# stm32_tiny_swd.net
KiCad netlist of a schematic drawn in EAGLE
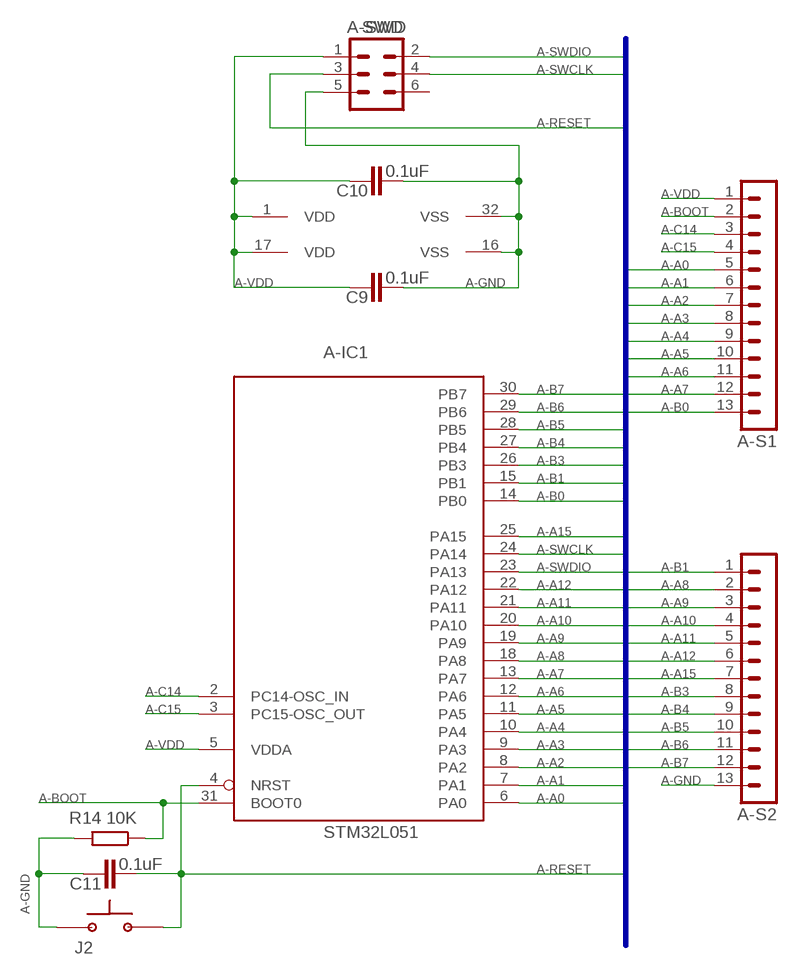
[diagram p0: schematic, sheet 1]

(export (version "E")
  (design (tool "Eeschema 10.0.6"))
  (components
    (comp (ref "A-IC1")
      (value "STM32L051")
      (footprint "eagle-import:LQFP32")
      (libsource (lib "eagle-import") (part "STM32L051KT8"))
    )
    (comp (ref "A-S1")
      (value "MA13-1")
      (footprint "eagle-import:MA13-1")
      (libsource (lib "eagle-import") (part "MA13-1"))
    )
    (comp (ref "A-S2")
      (value "MA13-1")
      (footprint "eagle-import:MA13-1")
      (libsource (lib "eagle-import") (part "MA13-1"))
    )
    (comp (ref "A-SWD")
      (value "SWD")
      (footprint "eagle-import:MA03-2")
      (libsource (lib "eagle-import") (part "MA03-2"))
    )
    (comp (ref "C9")
      (value "0.1uF")
      (footprint "eagle-import:C0805")
      (libsource (lib "eagle-import") (part "C-EUC0805"))
    )
    (comp (ref "C10")
      (value "0.1uF")
      (footprint "eagle-import:C0805")
      (libsource (lib "eagle-import") (part "C-EUC0805"))
    )
    (comp (ref "C11")
      (value "0.1uF")
      (footprint "eagle-import:C0805")
      (libsource (lib "eagle-import") (part "C-EUC0805"))
    )
    (comp (ref "J2")
      (value "BUTTON-FSM14JRT")
      (footprint "eagle-import:BUTTON-FSM14JRT")
      (libsource (lib "eagle-import") (part "BUTTON-FSM14JRT"))
    )
    (comp (ref "R14")
      (value "10K")
      (footprint "eagle-import:R0805")
      (libsource (lib "eagle-import") (part "R-EU_R0805"))
    )
  )
  (nets
    (net (code "1") (name "/A-A0") (class "Default")
      (node (ref "A-IC1") (pin "6") (pinfunction "PA0_6") (pintype "bidirectional"))
      (node (ref "A-S1") (pin "5") (pinfunction "5_5") (pintype "passive"))
    )
    (net (code "2") (name "/A-A1") (class "Default")
      (node (ref "A-IC1") (pin "7") (pinfunction "PA1_7") (pintype "bidirectional"))
      (node (ref "A-S1") (pin "6") (pinfunction "6_6") (pintype "passive"))
    )
    (net (code "3") (name "/A-A2") (class "Default")
      (node (ref "A-IC1") (pin "8") (pinfunction "PA2_8") (pintype "bidirectional"))
      (node (ref "A-S1") (pin "7") (pinfunction "7_7") (pintype "passive"))
    )
    (net (code "4") (name "/A-A3") (class "Default")
      (node (ref "A-IC1") (pin "9") (pinfunction "PA3_9") (pintype "bidirectional"))
      (node (ref "A-S1") (pin "8") (pinfunction "8_8") (pintype "passive"))
    )
    (net (code "5") (name "/A-A4") (class "Default")
      (node (ref "A-IC1") (pin "10") (pinfunction "PA4_10") (pintype "bidirectional"))
      (node (ref "A-S1") (pin "9") (pinfunction "9_9") (pintype "passive"))
    )
    (net (code "6") (name "/A-A5") (class "Default")
      (node (ref "A-IC1") (pin "11") (pinfunction "PA5_11") (pintype "bidirectional"))
      (node (ref "A-S1") (pin "10") (pinfunction "10_10") (pintype "passive"))
    )
    (net (code "7") (name "/A-A6") (class "Default")
      (node (ref "A-IC1") (pin "12") (pinfunction "PA6_12") (pintype "bidirectional"))
      (node (ref "A-S1") (pin "11") (pinfunction "11_11") (pintype "passive"))
    )
    (net (code "8") (name "/A-A7") (class "Default")
      (node (ref "A-IC1") (pin "13") (pinfunction "PA7_13") (pintype "bidirectional"))
      (node (ref "A-S1") (pin "12") (pinfunction "12_12") (pintype "passive"))
    )
    (net (code "9") (name "/A-A8") (class "Default")
      (node (ref "A-IC1") (pin "18") (pinfunction "PA8_18") (pintype "bidirectional"))
      (node (ref "A-S2") (pin "2") (pinfunction "2_2") (pintype "passive"))
    )
    (net (code "10") (name "/A-A9") (class "Default")
      (node (ref "A-IC1") (pin "19") (pinfunction "PA9_19") (pintype "bidirectional"))
      (node (ref "A-S2") (pin "3") (pinfunction "3_3") (pintype "passive"))
    )
    (net (code "11") (name "/A-A10") (class "Default")
      (node (ref "A-IC1") (pin "20") (pinfunction "PA10_20") (pintype "bidirectional"))
      (node (ref "A-S2") (pin "4") (pinfunction "4_4") (pintype "passive"))
    )
    (net (code "12") (name "/A-A11") (class "Default")
      (node (ref "A-IC1") (pin "21") (pinfunction "PA11_21") (pintype "bidirectional"))
      (node (ref "A-S2") (pin "5") (pinfunction "5_5") (pintype "passive"))
    )
    (net (code "13") (name "/A-A12") (class "Default")
      (node (ref "A-IC1") (pin "22") (pinfunction "PA12_22") (pintype "bidirectional"))
      (node (ref "A-S2") (pin "6") (pinfunction "6_6") (pintype "passive"))
    )
    (net (code "14") (name "/A-A15") (class "Default")
      (node (ref "A-IC1") (pin "25") (pinfunction "PA15_25") (pintype "bidirectional"))
      (node (ref "A-S2") (pin "7") (pinfunction "7_7") (pintype "passive"))
    )
    (net (code "15") (name "/A-B0") (class "Default")
      (node (ref "A-IC1") (pin "14") (pinfunction "PB0_14") (pintype "bidirectional"))
      (node (ref "A-S1") (pin "13") (pinfunction "13_13") (pintype "passive"))
    )
    (net (code "16") (name "/A-B1") (class "Default")
      (node (ref "A-IC1") (pin "15") (pinfunction "PB1_15") (pintype "bidirectional"))
      (node (ref "A-S2") (pin "1") (pinfunction "1_1") (pintype "passive"))
    )
    (net (code "17") (name "/A-B3") (class "Default")
      (node (ref "A-IC1") (pin "26") (pinfunction "PB3_26") (pintype "bidirectional"))
      (node (ref "A-S2") (pin "8") (pinfunction "8_8") (pintype "passive"))
    )
    (net (code "18") (name "/A-B4") (class "Default")
      (node (ref "A-IC1") (pin "27") (pinfunction "PB4_27") (pintype "bidirectional"))
      (node (ref "A-S2") (pin "9") (pinfunction "9_9") (pintype "passive"))
    )
    (net (code "19") (name "/A-B5") (class "Default")
      (node (ref "A-IC1") (pin "28") (pinfunction "PB5_28") (pintype "bidirectional"))
      (node (ref "A-S2") (pin "10") (pinfunction "10_10") (pintype "passive"))
    )
    (net (code "20") (name "/A-B6") (class "Default")
      (node (ref "A-IC1") (pin "29") (pinfunction "PB6_29") (pintype "bidirectional"))
      (node (ref "A-S2") (pin "11") (pinfunction "11_11") (pintype "passive"))
    )
    (net (code "21") (name "/A-B7") (class "Default")
      (node (ref "A-IC1") (pin "30") (pinfunction "PB7_30") (pintype "bidirectional"))
      (node (ref "A-S2") (pin "12") (pinfunction "12_12") (pintype "passive"))
    )
    (net (code "22") (name "/A-BOOT") (class "Default")
      (node (ref "A-IC1") (pin "31") (pinfunction "BOOT0_31") (pintype "input"))
      (node (ref "A-S1") (pin "2") (pinfunction "2_2") (pintype "passive"))
      (node (ref "R14") (pin "1") (pinfunction "1_1") (pintype "passive"))
    )
    (net (code "23") (name "/A-C14") (class "Default")
      (node (ref "A-IC1") (pin "2") (pinfunction "PC14-OSC_IN_2") (pintype "bidirectional"))
      (node (ref "A-S1") (pin "3") (pinfunction "3_3") (pintype "passive"))
    )
    (net (code "24") (name "/A-C15") (class "Default")
      (node (ref "A-IC1") (pin "3") (pinfunction "PC15-OSC_OUT_3") (pintype "bidirectional"))
      (node (ref "A-S1") (pin "4") (pinfunction "4_4") (pintype "passive"))
    )
    (net (code "25") (name "/A-GND") (class "Default")
      (node (ref "A-IC1") (pin "16") (pinfunction "VSS_16") (pintype "power_in"))
      (node (ref "A-IC1") (pin "32") (pinfunction "VSS_32") (pintype "power_in"))
      (node (ref "A-S2") (pin "13") (pinfunction "13_13") (pintype "passive"))
      (node (ref "A-SWD") (pin "5") (pinfunction "5_5") (pintype "passive"))
      (node (ref "C10") (pin "2") (pinfunction "2_2") (pintype "passive"))
      (node (ref "C11") (pin "1") (pinfunction "1_1") (pintype "passive"))
      (node (ref "C9") (pin "2") (pinfunction "2_2") (pintype "passive"))
      (node (ref "J2") (pin "P$1") (pinfunction "1_P$1") (pintype "bidirectional"))
      (node (ref "R14") (pin "2") (pinfunction "2_2") (pintype "passive"))
    )
    (net (code "26") (name "/A-RESET") (class "Default")
      (node (ref "A-IC1") (pin "4") (pinfunction "NRST_4") (pintype "bidirectional"))
      (node (ref "A-SWD") (pin "3") (pinfunction "3_3") (pintype "passive"))
      (node (ref "C11") (pin "2") (pinfunction "2_2") (pintype "passive"))
      (node (ref "J2") (pin "P$2") (pinfunction "2_P$2") (pintype "bidirectional"))
    )
    (net (code "27") (name "/A-SWCLK") (class "Default")
      (node (ref "A-IC1") (pin "24") (pinfunction "PA14_24") (pintype "bidirectional"))
      (node (ref "A-SWD") (pin "4") (pinfunction "4_4") (pintype "passive"))
    )
    (net (code "28") (name "/A-SWDIO") (class "Default")
      (node (ref "A-IC1") (pin "23") (pinfunction "PA13_23") (pintype "bidirectional"))
      (node (ref "A-SWD") (pin "2") (pinfunction "2_2") (pintype "passive"))
    )
    (net (code "29") (name "/A-VDD") (class "Default")
      (node (ref "A-IC1") (pin "1") (pinfunction "VDD_1") (pintype "power_in"))
      (node (ref "A-IC1") (pin "17") (pinfunction "VDD_17") (pintype "power_in"))
      (node (ref "A-IC1") (pin "5") (pinfunction "VDDA_5") (pintype "power_in"))
      (node (ref "A-S1") (pin "1") (pinfunction "1_1") (pintype "passive"))
      (node (ref "A-SWD") (pin "1") (pinfunction "1_1") (pintype "passive"))
      (node (ref "C10") (pin "1") (pinfunction "1_1") (pintype "passive"))
      (node (ref "C9") (pin "1") (pinfunction "1_1") (pintype "passive"))
    )
    (net (code "30") (name "unconnected-(A-SWD-Pad6)") (class "Default")
      (node (ref "A-SWD") (pin "6") (pinfunction "6_6") (pintype "passive"))
    )
  )
)
